# HDMI.net
KiCad netlist of a schematic drawn in Altium Designer
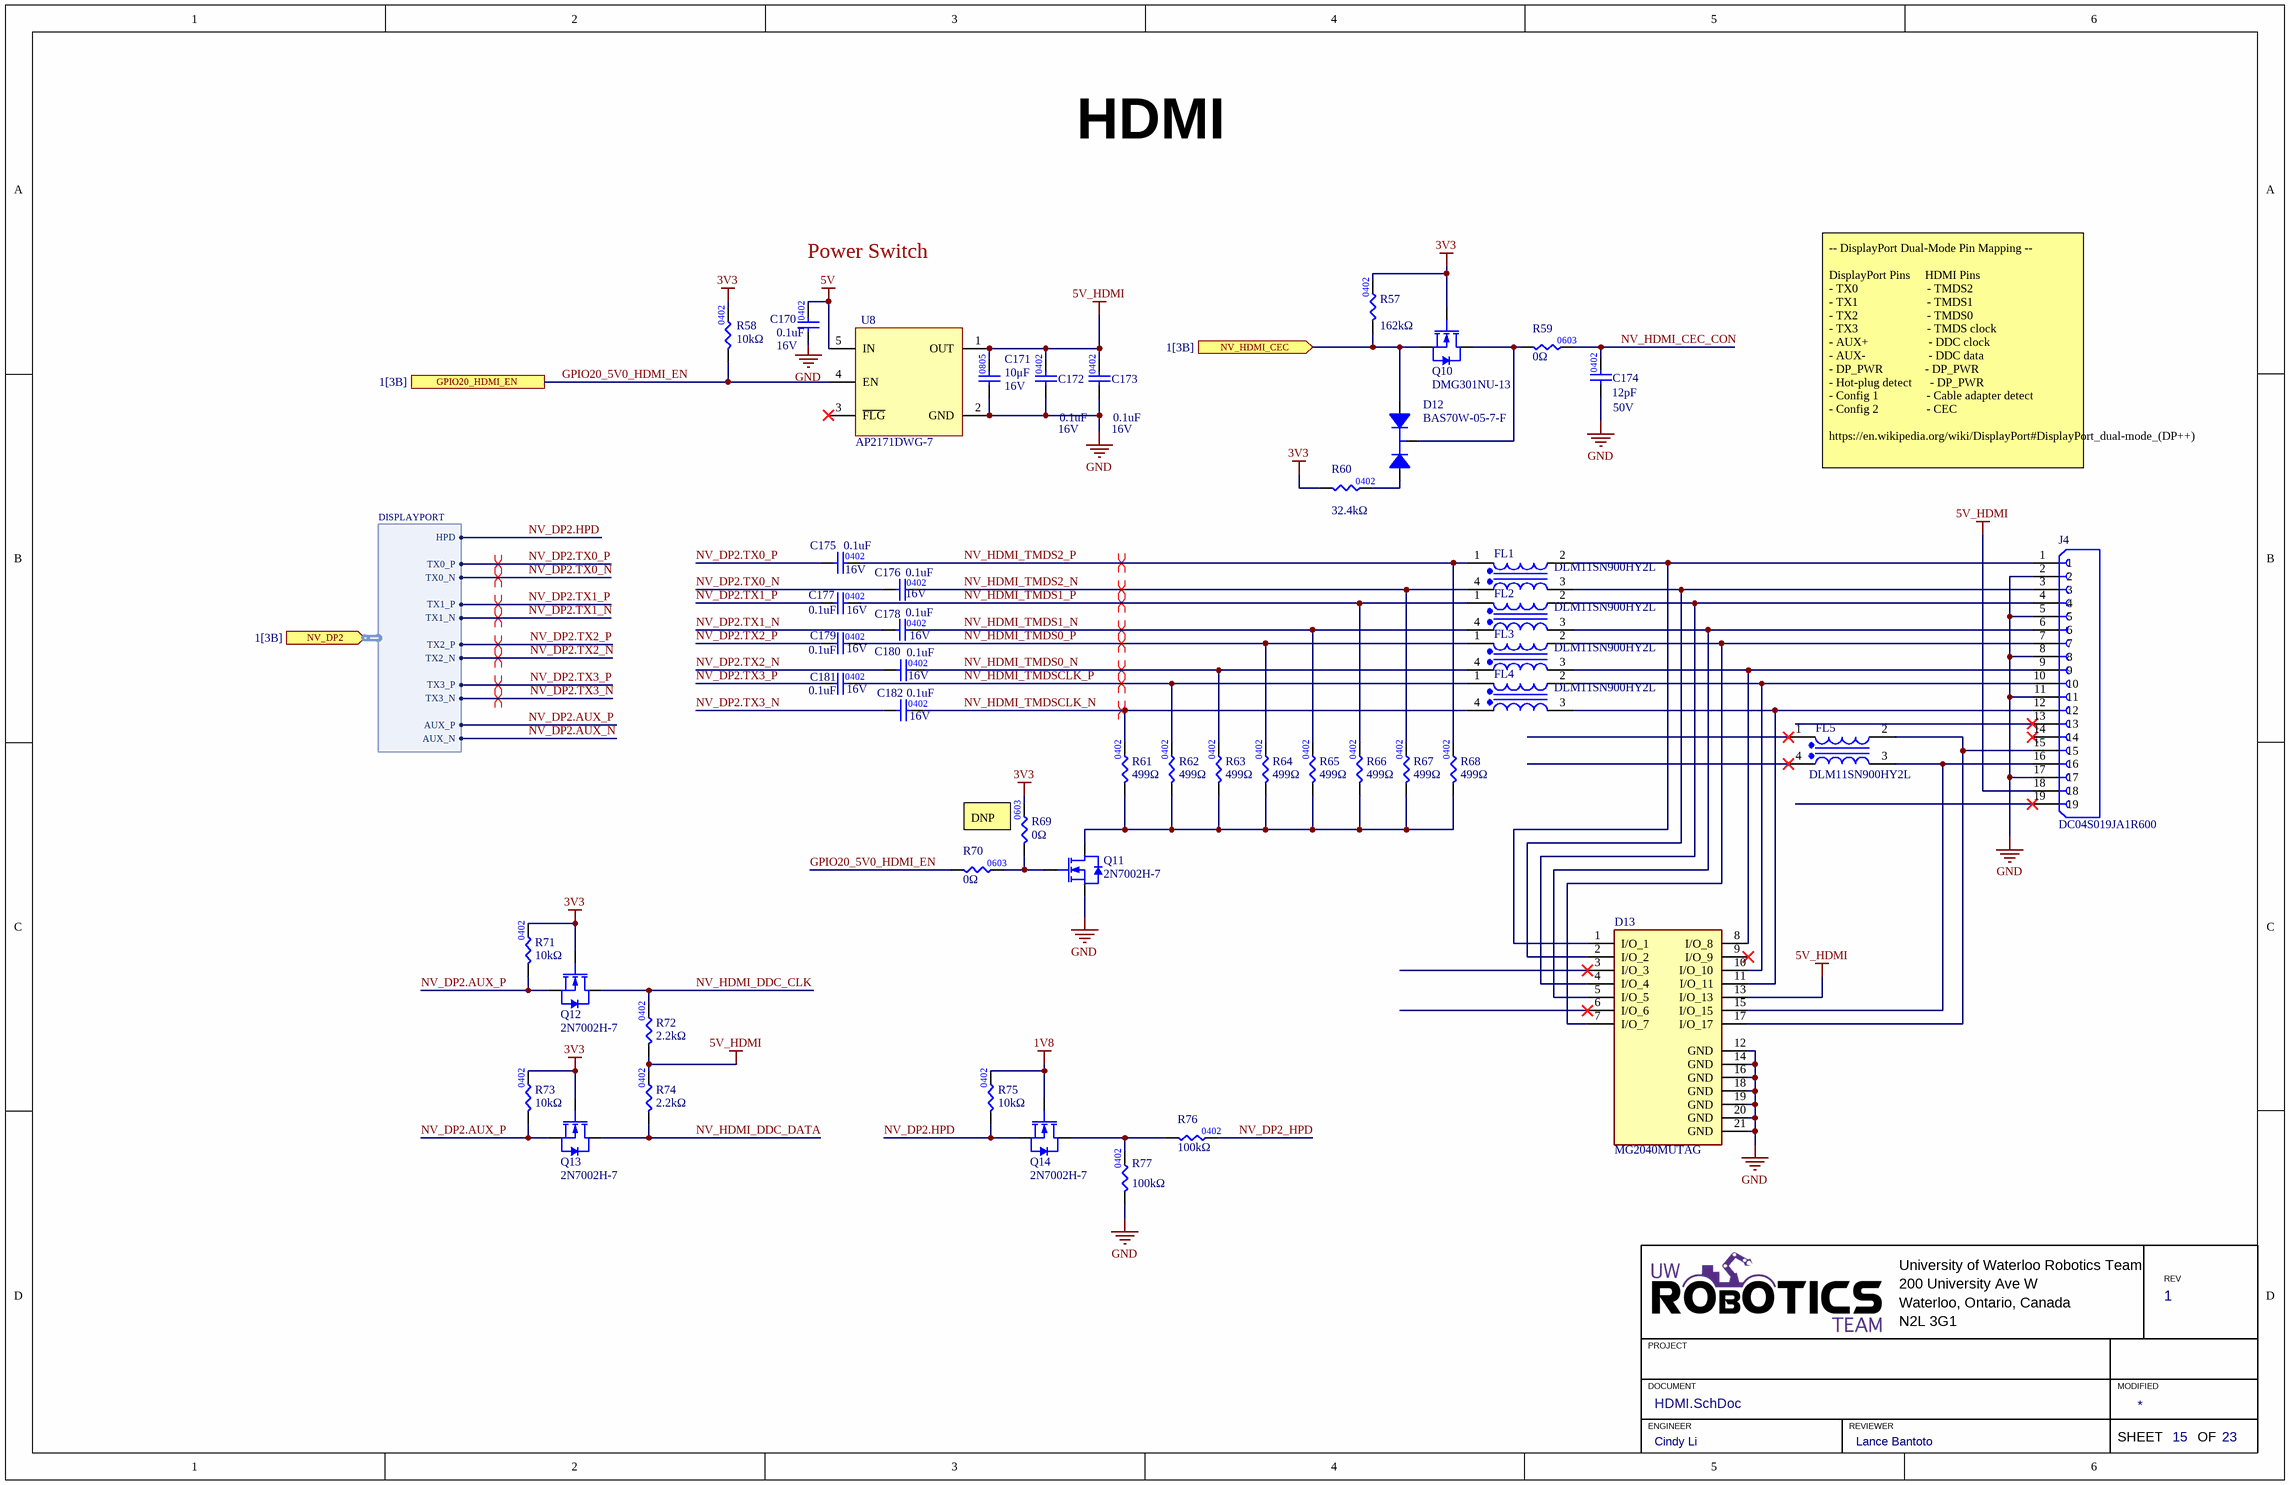
[diagram p0: HDMI.SchDoc]

(export (version "E")
  (design (tool "Eeschema 10.0.6"))
  (components
    (comp (ref "C170")
      (value "CAP_0.1uF_16V_X7R_0402")
      (footprint "CAP0402")
      (description "Ceramic Capacitor, Ceramic")
      (fields
        (field (name "MANUFACTURER") "Taiyo Yuden")
        (field (name "MANUFACTURER PART NUMBER") "LMK212AC6106MD-T")
        (field (name "RATED DC VOLTAGE (URDC)") "16V")
        (field (name "CAPACITANCE") "0.1uF")
      )
      (libsource (lib "UWRT_Schematic_Library_2020") (part "CAP_0.1uF_16V_X7R_0402"))
    )
    (comp (ref "C171")
      (value "10μF")
      (footprint "CAP2012")
      (description "CAP CER 10UF 16V X5R 0805")
      (fields (field (name "VOLTAGE RATING") "16V") (field (name "Comment") "CAP_10uF_16V_0805"))
      (libsource (lib "UWRT_Schematic_Library_2020") (part "CAP_10uF_16V_0805"))
    )
    (comp (ref "C172")
      (value "CAP_0.1uF_16V_X7R_0402")
      (footprint "CAP0402")
      (description "Ceramic Capacitor, Ceramic")
      (fields
        (field (name "MANUFACTURER") "Taiyo Yuden")
        (field (name "MANUFACTURER PART NUMBER") "LMK212AC6106MD-T")
        (field (name "RATED DC VOLTAGE (URDC)") "16V")
        (field (name "CAPACITANCE") "0.1uF")
      )
      (libsource (lib "UWRT_Schematic_Library_2020") (part "CAP_0.1uF_16V_X7R_0402"))
    )
    (comp (ref "C173")
      (value "CAP_0.1uF_16V_X7R_0402")
      (footprint "CAP0402")
      (description "Ceramic Capacitor, Ceramic")
      (fields
        (field (name "MANUFACTURER") "Taiyo Yuden")
        (field (name "MANUFACTURER PART NUMBER") "LMK212AC6106MD-T")
        (field (name "RATED DC VOLTAGE (URDC)") "16V")
        (field (name "CAPACITANCE") "0.1uF")
      )
      (libsource (lib "UWRT_Schematic_Library_2020") (part "CAP_0.1uF_16V_X7R_0402"))
    )
    (comp (ref "C174")
      (value "12pF")
      (footprint "CAP0402")
      (description "CAP CER 12PF 50V C0G 0402")
      (fields
        (field (name "TOLERANCE") "±5%")
        (field (name "VOLTAGE RATING") "50V")
        (field (name "Comment") "CAP_12pF_50V_0402")
      )
      (libsource (lib "UWRT_Schematic_Library_2020") (part "CAP_12pF_50V_0402"))
    )
    (comp (ref "C175")
      (value "CAP_0.1uF_16V_X7R_0402")
      (footprint "CAP0402")
      (description "Ceramic Capacitor, Ceramic")
      (fields
        (field (name "CAPACITANCE") "0.1uF")
        (field (name "MANUFACTURER") "Taiyo Yuden")
        (field (name "MANUFACTURER PART NUMBER") "LMK212AC6106MD-T")
        (field (name "RATED DC VOLTAGE (URDC)") "16V")
      )
      (libsource (lib "UWRT_Schematic_Library_2020") (part "CAP_0.1uF_16V_X7R_0402"))
    )
    (comp (ref "C176")
      (value "CAP_0.1uF_16V_X7R_0402")
      (footprint "CAP0402")
      (description "Ceramic Capacitor, Ceramic")
      (fields
        (field (name "CAPACITANCE") "0.1uF")
        (field (name "MANUFACTURER") "Taiyo Yuden")
        (field (name "MANUFACTURER PART NUMBER") "LMK212AC6106MD-T")
        (field (name "RATED DC VOLTAGE (URDC)") "16V")
      )
      (libsource (lib "UWRT_Schematic_Library_2020") (part "CAP_0.1uF_16V_X7R_0402"))
    )
    (comp (ref "C177")
      (value "CAP_0.1uF_16V_X7R_0402")
      (footprint "CAP0402")
      (description "Ceramic Capacitor, Ceramic")
      (fields
        (field (name "CAPACITANCE") "0.1uF")
        (field (name "MANUFACTURER") "Taiyo Yuden")
        (field (name "MANUFACTURER PART NUMBER") "LMK212AC6106MD-T")
        (field (name "RATED DC VOLTAGE (URDC)") "16V")
      )
      (libsource (lib "UWRT_Schematic_Library_2020") (part "CAP_0.1uF_16V_X7R_0402"))
    )
    (comp (ref "C178")
      (value "CAP_0.1uF_16V_X7R_0402")
      (footprint "CAP0402")
      (description "Ceramic Capacitor, Ceramic")
      (fields
        (field (name "CAPACITANCE") "0.1uF")
        (field (name "MANUFACTURER") "Taiyo Yuden")
        (field (name "MANUFACTURER PART NUMBER") "LMK212AC6106MD-T")
        (field (name "RATED DC VOLTAGE (URDC)") "16V")
      )
      (libsource (lib "UWRT_Schematic_Library_2020") (part "CAP_0.1uF_16V_X7R_0402"))
    )
    (comp (ref "C179")
      (value "CAP_0.1uF_16V_X7R_0402")
      (footprint "CAP0402")
      (description "Ceramic Capacitor, Ceramic")
      (fields
        (field (name "CAPACITANCE") "0.1uF")
        (field (name "MANUFACTURER") "Taiyo Yuden")
        (field (name "MANUFACTURER PART NUMBER") "LMK212AC6106MD-T")
        (field (name "RATED DC VOLTAGE (URDC)") "16V")
      )
      (libsource (lib "UWRT_Schematic_Library_2020") (part "CAP_0.1uF_16V_X7R_0402"))
    )
    (comp (ref "C180")
      (value "CAP_0.1uF_16V_X7R_0402")
      (footprint "CAP0402")
      (description "Ceramic Capacitor, Ceramic")
      (fields
        (field (name "CAPACITANCE") "0.1uF")
        (field (name "MANUFACTURER") "Taiyo Yuden")
        (field (name "MANUFACTURER PART NUMBER") "LMK212AC6106MD-T")
        (field (name "RATED DC VOLTAGE (URDC)") "16V")
      )
      (libsource (lib "UWRT_Schematic_Library_2020") (part "CAP_0.1uF_16V_X7R_0402"))
    )
    (comp (ref "C181")
      (value "CAP_0.1uF_16V_X7R_0402")
      (footprint "CAP0402")
      (description "Ceramic Capacitor, Ceramic")
      (fields
        (field (name "CAPACITANCE") "0.1uF")
        (field (name "MANUFACTURER") "Taiyo Yuden")
        (field (name "MANUFACTURER PART NUMBER") "LMK212AC6106MD-T")
        (field (name "RATED DC VOLTAGE (URDC)") "16V")
      )
      (libsource (lib "UWRT_Schematic_Library_2020") (part "CAP_0.1uF_16V_X7R_0402"))
    )
    (comp (ref "C182")
      (value "CAP_0.1uF_16V_X7R_0402")
      (footprint "CAP0402")
      (description "Ceramic Capacitor, Ceramic")
      (fields
        (field (name "CAPACITANCE") "0.1uF")
        (field (name "MANUFACTURER") "Taiyo Yuden")
        (field (name "MANUFACTURER PART NUMBER") "LMK212AC6106MD-T")
        (field (name "RATED DC VOLTAGE (URDC)") "16V")
      )
      (libsource (lib "UWRT_Schematic_Library_2020") (part "CAP_0.1uF_16V_X7R_0402"))
    )
    (comp (ref "D12")
      (value "BAS70W-05-7-F")
      (footprint "SOT323_BAS70W-05-7-F")
      (description "DIODE ARRAY SCHOTTKY 70V SOT323")
      (libsource (lib "UWRT_Schematic_Library_2020") (part "BAS70W-05-7-F"))
    )
    (comp (ref "D13")
      (value "MG2040MUTAG")
      (footprint "UWRT_Footprint_Library_2020:DIO_MG2040MUTAG")
      (description "10V Clamp 1A (8/20µs) Ipp Tvs Diode Surface Mount 18-UDFN (5.5x1.5)")
      (libsource (lib "UWRT_Schematic_Library_2020") (part "MG2040MUTAG"))
    )
    (comp (ref "FL1")
      (value "DLM11SN900HY2L")
      (footprint "UWRT_Footprint_Library_2020:FIL_DLM11SN900HY2L")
      (description "2 Line Common Mode Choke Surface Mount 90 Ohms @ 100 MHz 100mA DCR 1.38Ohm")
      (libsource (lib "UWRT_Schematic_Library_2020") (part "DLM11SN900HY2L"))
    )
    (comp (ref "FL2")
      (value "DLM11SN900HY2L")
      (footprint "UWRT_Footprint_Library_2020:FIL_DLM11SN900HY2L")
      (description "2 Line Common Mode Choke Surface Mount 90 Ohms @ 100 MHz 100mA DCR 1.38Ohm")
      (libsource (lib "UWRT_Schematic_Library_2020") (part "DLM11SN900HY2L"))
    )
    (comp (ref "FL3")
      (value "DLM11SN900HY2L")
      (footprint "UWRT_Footprint_Library_2020:FIL_DLM11SN900HY2L")
      (description "2 Line Common Mode Choke Surface Mount 90 Ohms @ 100 MHz 100mA DCR 1.38Ohm")
      (libsource (lib "UWRT_Schematic_Library_2020") (part "DLM11SN900HY2L"))
    )
    (comp (ref "FL4")
      (value "DLM11SN900HY2L")
      (footprint "UWRT_Footprint_Library_2020:FIL_DLM11SN900HY2L")
      (description "2 Line Common Mode Choke Surface Mount 90 Ohms @ 100 MHz 100mA DCR 1.38Ohm")
      (libsource (lib "UWRT_Schematic_Library_2020") (part "DLM11SN900HY2L"))
    )
    (comp (ref "FL5")
      (value "DLM11SN900HY2L")
      (footprint "UWRT_Footprint_Library_2020:FIL_DLM11SN900HY2L")
      (description "2 Line Common Mode Choke Surface Mount 90 Ohms @ 100 MHz 100mA DCR 1.38Ohm")
      (libsource (lib "UWRT_Schematic_Library_2020") (part "DLM11SN900HY2L"))
    )
    (comp (ref "J4")
      (value "DC04S019JA1R600")
      (footprint "UWRT_Footprint_Library_2020:JAE_DC04S019JA1R600")
      (description "HDMI HDMI 2.1 Receptacle Connector 19 Position Surface Mount, Right Angle; Through Hole")
      (libsource (lib "UWRT_Schematic_Library_2020") (part "DC04S019JA1R600"))
    )
    (comp (ref "Q10")
      (value "DMG301NU-13")
      (footprint "SOT23-3")
      (description "MOSFET N-CH 25V 260MA SOT23")
      (fields (field (name "MANUFACTURER PART NUMBER 1") "DMG301NU-13"))
      (libsource (lib "UWRT_Schematic_Library_2020") (part "DMG301NU-13"))
    )
    (comp (ref "Q11")
      (value "2N7002H-7")
      (footprint "SOT23-3")
      (description "MOSFET N-CH 60V 170MA SOT23")
      (fields (field (name "MANUFACTURER PART NUMBER 1") "2N7002H-7"))
      (libsource (lib "UWRT_Schematic_Library_2020") (part "2N7002H-7"))
    )
    (comp (ref "Q12")
      (value "2N7002H-7")
      (footprint "SOT23-3")
      (description "MOSFET N-CH 60V 170MA SOT23")
      (fields (field (name "MANUFACTURER PART NUMBER 1") "2N7002H-7"))
      (libsource (lib "UWRT_Schematic_Library_2020") (part "2N7002H-7"))
    )
    (comp (ref "Q13")
      (value "2N7002H-7")
      (footprint "SOT23-3")
      (description "MOSFET N-CH 60V 170MA SOT23")
      (fields (field (name "MANUFACTURER PART NUMBER 1") "2N7002H-7"))
      (libsource (lib "UWRT_Schematic_Library_2020") (part "2N7002H-7"))
    )
    (comp (ref "Q14")
      (value "2N7002H-7")
      (footprint "SOT23-3")
      (description "MOSFET N-CH 60V 170MA SOT23")
      (fields (field (name "MANUFACTURER PART NUMBER 1") "2N7002H-7"))
      (libsource (lib "UWRT_Schematic_Library_2020") (part "2N7002H-7"))
    )
    (comp (ref "R57")
      (value "162kΩ")
      (footprint "RES0402")
      (description "RES 162K OHM 1% 1/16W 0402")
      (fields (field (name "POWER") "0.063W, 1/16W") (field (name "TOLERANCE") "1%"))
      (libsource (lib "UWRT_Schematic_Library_2020") (part "RES_162kΩ_0402_1%"))
    )
    (comp (ref "R58")
      (value "10kΩ")
      (footprint "RES0402")
      (description "RES SMD 10K OHM 1% 1/16W 0402")
      (fields (field (name "POWER") "0.063W, 1/16W") (field (name "TOLERANCE") "1%"))
      (libsource (lib "UWRT_Schematic_Library_2020") (part "RES_10kΩ_0402_1%"))
    )
    (comp (ref "R59")
      (value "0Ω")
      (footprint "RES0603")
      (description "RES 0 OHM JUMPER 1/10W 0603")
      (fields (field (name "Comment") "RES_0Ω_0603"))
      (libsource (lib "UWRT_Schematic_Library_2020") (part "RES_0Ω_0603"))
    )
    (comp (ref "R60")
      (value "32.4kΩ")
      (footprint "RES0402")
      (description "RES SMD 32.4K OHM 1% 1/10W 0402")
      (fields (field (name "POWER") "0.1W, 1/10W") (field (name "TOLERANCE") "1%"))
      (libsource (lib "UWRT_Schematic_Library_2020") (part "RES_32.4kΩ_0402_1%"))
    )
    (comp (ref "R61")
      (value "499Ω")
      (footprint "RES0402")
      (description "RES 499 OHM 1% 1/16W 0402")
      (fields (field (name "POWER") "0.063W, 1/16W") (field (name "TOLERANCE") "1%"))
      (libsource (lib "UWRT_Schematic_Library_2020") (part "RES_499Ω_0402_1%"))
    )
    (comp (ref "R62")
      (value "499Ω")
      (footprint "RES0402")
      (description "RES 499 OHM 1% 1/16W 0402")
      (fields (field (name "POWER") "0.063W, 1/16W") (field (name "TOLERANCE") "1%"))
      (libsource (lib "UWRT_Schematic_Library_2020") (part "RES_499Ω_0402_1%"))
    )
    (comp (ref "R63")
      (value "499Ω")
      (footprint "RES0402")
      (description "RES 499 OHM 1% 1/16W 0402")
      (fields (field (name "POWER") "0.063W, 1/16W") (field (name "TOLERANCE") "1%"))
      (libsource (lib "UWRT_Schematic_Library_2020") (part "RES_499Ω_0402_1%"))
    )
    (comp (ref "R64")
      (value "499Ω")
      (footprint "RES0402")
      (description "RES 499 OHM 1% 1/16W 0402")
      (fields (field (name "POWER") "0.063W, 1/16W") (field (name "TOLERANCE") "1%"))
      (libsource (lib "UWRT_Schematic_Library_2020") (part "RES_499Ω_0402_1%"))
    )
    (comp (ref "R65")
      (value "499Ω")
      (footprint "RES0402")
      (description "RES 499 OHM 1% 1/16W 0402")
      (fields (field (name "POWER") "0.063W, 1/16W") (field (name "TOLERANCE") "1%"))
      (libsource (lib "UWRT_Schematic_Library_2020") (part "RES_499Ω_0402_1%"))
    )
    (comp (ref "R66")
      (value "499Ω")
      (footprint "RES0402")
      (description "RES 499 OHM 1% 1/16W 0402")
      (fields (field (name "POWER") "0.063W, 1/16W") (field (name "TOLERANCE") "1%"))
      (libsource (lib "UWRT_Schematic_Library_2020") (part "RES_499Ω_0402_1%"))
    )
    (comp (ref "R67")
      (value "499Ω")
      (footprint "RES0402")
      (description "RES 499 OHM 1% 1/16W 0402")
      (fields (field (name "POWER") "0.063W, 1/16W") (field (name "TOLERANCE") "1%"))
      (libsource (lib "UWRT_Schematic_Library_2020") (part "RES_499Ω_0402_1%"))
    )
    (comp (ref "R68")
      (value "499Ω")
      (footprint "RES0402")
      (description "RES 499 OHM 1% 1/16W 0402")
      (fields (field (name "POWER") "0.063W, 1/16W") (field (name "TOLERANCE") "1%"))
      (libsource (lib "UWRT_Schematic_Library_2020") (part "RES_499Ω_0402_1%"))
    )
    (comp (ref "R69")
      (value "0Ω")
      (footprint "RES0603")
      (description "RES 0 OHM JUMPER 1/10W 0603")
      (fields (field (name "Comment") "RES_0Ω_0603"))
      (libsource (lib "UWRT_Schematic_Library_2020") (part "RES_0Ω_0603"))
    )
    (comp (ref "R70")
      (value "0Ω")
      (footprint "RES0603")
      (description "RES 0 OHM JUMPER 1/10W 0603")
      (fields (field (name "Comment") "RES_0Ω_0603"))
      (libsource (lib "UWRT_Schematic_Library_2020") (part "RES_0Ω_0603"))
    )
    (comp (ref "R71")
      (value "10kΩ")
      (footprint "RES0402")
      (description "RES SMD 10K OHM 1% 1/16W 0402")
      (fields (field (name "POWER") "0.063W, 1/16W") (field (name "TOLERANCE") "1%"))
      (libsource (lib "UWRT_Schematic_Library_2020") (part "RES_10kΩ_0402_1%"))
    )
    (comp (ref "R72")
      (value "2.2kΩ")
      (footprint "RES0402")
      (description "RES SMD 2.2K OHM 5% 1/10W 0402")
      (fields (field (name "Comment") "RES_2.2kΩ_0402_5%"))
      (libsource (lib "UWRT_Schematic_Library_2020") (part "RES_2.2kΩ_0402_5%"))
    )
    (comp (ref "R73")
      (value "10kΩ")
      (footprint "RES0402")
      (description "RES SMD 10K OHM 1% 1/16W 0402")
      (fields (field (name "POWER") "0.063W, 1/16W") (field (name "TOLERANCE") "1%"))
      (libsource (lib "UWRT_Schematic_Library_2020") (part "RES_10kΩ_0402_1%"))
    )
    (comp (ref "R74")
      (value "2.2kΩ")
      (footprint "RES0402")
      (description "RES SMD 2.2K OHM 5% 1/10W 0402")
      (fields (field (name "Comment") "RES_2.2kΩ_0402_5%"))
      (libsource (lib "UWRT_Schematic_Library_2020") (part "RES_2.2kΩ_0402_5%"))
    )
    (comp (ref "R75")
      (value "10kΩ")
      (footprint "RES0402")
      (description "RES SMD 10K OHM 1% 1/16W 0402")
      (fields (field (name "POWER") "0.063W, 1/16W") (field (name "TOLERANCE") "1%"))
      (libsource (lib "UWRT_Schematic_Library_2020") (part "RES_10kΩ_0402_1%"))
    )
    (comp (ref "R76")
      (value "100kΩ")
      (footprint "RES0402")
      (description "RES SMD 100K OHM 5% 1/10W 0402")
      (fields (field (name "POWER") "0.1W, 1/10W") (field (name "TOLERANCE") "5%"))
      (libsource (lib "UWRT_Schematic_Library_2020") (part "RES_100kΩ_0402_5%"))
    )
    (comp (ref "R77")
      (value "100kΩ")
      (footprint "RES0402")
      (description "RES SMD 100K OHM 5% 1/10W 0402")
      (fields (field (name "POWER") "0.1W, 1/10W") (field (name "TOLERANCE") "5%"))
      (libsource (lib "UWRT_Schematic_Library_2020") (part "RES_100kΩ_0402_5%"))
    )
    (comp (ref "U8")
      (value "AP2171DWG-7")
      (footprint "AP2171DWG-7")
      (description "Power Switch/Driver 1:1 P-Channel 1A SOT-25")
      (libsource (lib "UWRT_Schematic_Library_2020") (part "AP2171DWG-7"))
    )
  )
  (nets
    (net (code "2") (name "/GPIO20_5V0_HDMI_EN") (class "Default")
      (node (ref "R58") (pin "1") (pinfunction "1_1") (pintype "passive"))
      (node (ref "R70") (pin "1") (pinfunction "1_1") (pintype "passive"))
      (node (ref "U8") (pin "4") (pinfunction "EN_4") (pintype "passive"))
    )
    (net (code "4") (name "/NV_DP2.AUX_P") (class "Default")
      (node (ref "Q12") (pin "2") (pinfunction "SOURCE_2") (pintype "passive"))
      (node (ref "Q13") (pin "2") (pinfunction "SOURCE_2") (pintype "passive"))
      (node (ref "R71") (pin "1") (pinfunction "1_1") (pintype "passive"))
      (node (ref "R73") (pin "1") (pinfunction "1_1") (pintype "passive"))
    )
    (net (code "5") (name "/NV_DP2.HPD") (class "Default")
      (node (ref "Q14") (pin "2") (pinfunction "SOURCE_2") (pintype "passive"))
      (node (ref "R75") (pin "1") (pinfunction "1_1") (pintype "passive"))
    )
    (net (code "6") (name "/NV_DP2.TX0_N") (class "Default")
      (node (ref "C176") (pin "1") (pinfunction "1_1") (pintype "passive"))
    )
    (net (code "7") (name "/NV_DP2.TX0_P") (class "Default")
      (node (ref "C175") (pin "1") (pinfunction "1_1") (pintype "passive"))
    )
    (net (code "8") (name "/NV_DP2.TX1_N") (class "Default")
      (node (ref "C178") (pin "1") (pinfunction "1_1") (pintype "passive"))
    )
    (net (code "9") (name "/NV_DP2.TX1_P") (class "Default")
      (node (ref "C177") (pin "1") (pinfunction "1_1") (pintype "passive"))
    )
    (net (code "10") (name "/NV_DP2.TX2_N") (class "Default")
      (node (ref "C180") (pin "1") (pinfunction "1_1") (pintype "passive"))
    )
    (net (code "11") (name "/NV_DP2.TX2_P") (class "Default")
      (node (ref "C179") (pin "1") (pinfunction "1_1") (pintype "passive"))
    )
    (net (code "12") (name "/NV_DP2.TX3_N") (class "Default")
      (node (ref "C182") (pin "1") (pinfunction "1_1") (pintype "passive"))
    )
    (net (code "13") (name "/NV_DP2.TX3_P") (class "Default")
      (node (ref "C181") (pin "1") (pinfunction "1_1") (pintype "passive"))
    )
    (net (code "14") (name "/NV_DP2_HPD") (class "Default")
      (node (ref "R76") (pin "2") (pinfunction "2_2") (pintype "passive"))
    )
    (net (code "15") (name "/NV_HDMI_CEC") (class "Default")
      (node (ref "D12") (pin "2") (pintype "passive"))
      (node (ref "Q10") (pin "2") (pinfunction "SOURCE_2") (pintype "passive"))
      (node (ref "R57") (pin "1") (pinfunction "1_1") (pintype "passive"))
    )
    (net (code "16") (name "/NV_HDMI_CEC_CON") (class "Default")
      (node (ref "C174") (pin "2") (pinfunction "2_2") (pintype "passive"))
      (node (ref "R59") (pin "2") (pinfunction "2_2") (pintype "passive"))
    )
    (net (code "17") (name "/NV_HDMI_DDC_CLK") (class "Default")
      (node (ref "Q12") (pin "3") (pinfunction "DRAIN_3") (pintype "passive"))
      (node (ref "R72") (pin "2") (pinfunction "2_2") (pintype "passive"))
    )
    (net (code "18") (name "/NV_HDMI_DDC_DATA") (class "Default")
      (node (ref "Q13") (pin "3") (pinfunction "DRAIN_3") (pintype "passive"))
      (node (ref "R74") (pin "1") (pinfunction "1_1") (pintype "passive"))
    )
    (net (code "19") (name "/NV_HDMI_TMDS0_N") (class "Default")
      (node (ref "C180") (pin "2") (pinfunction "2_2") (pintype "passive"))
      (node (ref "FL3") (pin "4") (pinfunction "4_4") (pintype "passive"))
      (node (ref "R63") (pin "2") (pinfunction "2_2") (pintype "passive"))
    )
    (net (code "20") (name "/NV_HDMI_TMDS0_P") (class "Default")
      (node (ref "C179") (pin "2") (pinfunction "2_2") (pintype "passive"))
      (node (ref "FL3") (pin "1") (pinfunction "1_1") (pintype "passive"))
      (node (ref "R64") (pin "2") (pinfunction "2_2") (pintype "passive"))
    )
    (net (code "21") (name "/NV_HDMI_TMDS1_N") (class "Default")
      (node (ref "C178") (pin "2") (pinfunction "2_2") (pintype "passive"))
      (node (ref "FL2") (pin "4") (pinfunction "4_4") (pintype "passive"))
      (node (ref "R65") (pin "2") (pinfunction "2_2") (pintype "passive"))
    )
    (net (code "22") (name "/NV_HDMI_TMDS1_P") (class "Default")
      (node (ref "C177") (pin "2") (pinfunction "2_2") (pintype "passive"))
      (node (ref "FL2") (pin "1") (pinfunction "1_1") (pintype "passive"))
      (node (ref "R66") (pin "2") (pinfunction "2_2") (pintype "passive"))
    )
    (net (code "23") (name "/NV_HDMI_TMDS2_N") (class "Default")
      (node (ref "C176") (pin "2") (pinfunction "2_2") (pintype "passive"))
      (node (ref "FL1") (pin "4") (pinfunction "4_4") (pintype "passive"))
      (node (ref "R67") (pin "2") (pinfunction "2_2") (pintype "passive"))
    )
    (net (code "24") (name "/NV_HDMI_TMDS2_P") (class "Default")
      (node (ref "C175") (pin "2") (pinfunction "2_2") (pintype "passive"))
      (node (ref "FL1") (pin "1") (pinfunction "1_1") (pintype "passive"))
      (node (ref "R68") (pin "2") (pinfunction "2_2") (pintype "passive"))
    )
    (net (code "25") (name "/NV_HDMI_TMDSCLK_N") (class "Default")
      (node (ref "C182") (pin "2") (pinfunction "2_2") (pintype "passive"))
      (node (ref "FL4") (pin "4") (pinfunction "4_4") (pintype "passive"))
      (node (ref "R61") (pin "2") (pinfunction "2_2") (pintype "passive"))
    )
    (net (code "26") (name "/NV_HDMI_TMDSCLK_P") (class "Default")
      (node (ref "C181") (pin "2") (pinfunction "2_2") (pintype "passive"))
      (node (ref "FL4") (pin "1") (pinfunction "1_1") (pintype "passive"))
      (node (ref "R62") (pin "2") (pinfunction "2_2") (pintype "passive"))
    )
    (net (code "28") (name "1V8") (class "Default")
      (node (ref "Q14") (pin "1") (pinfunction "GATE_1") (pintype "passive"))
      (node (ref "R75") (pin "2") (pinfunction "2_2") (pintype "passive"))
    )
    (net (code "29") (name "3V3") (class "Default")
      (node (ref "Q10") (pin "1") (pinfunction "GATE_1") (pintype "passive"))
      (node (ref "Q12") (pin "1") (pinfunction "GATE_1") (pintype "passive"))
      (node (ref "Q13") (pin "1") (pinfunction "GATE_1") (pintype "passive"))
      (node (ref "R57") (pin "2") (pinfunction "2_2") (pintype "passive"))
      (node (ref "R58") (pin "2") (pinfunction "2_2") (pintype "passive"))
      (node (ref "R60") (pin "1") (pinfunction "1_1") (pintype "passive"))
      (node (ref "R69") (pin "2") (pinfunction "2_2") (pintype "passive"))
      (node (ref "R71") (pin "2") (pinfunction "2_2") (pintype "passive"))
      (node (ref "R73") (pin "2") (pinfunction "2_2") (pintype "passive"))
    )
    (net (code "30") (name "5V") (class "Default")
      (node (ref "C170") (pin "2") (pinfunction "2_2") (pintype "passive"))
      (node (ref "U8") (pin "5") (pinfunction "IN_5") (pintype "passive"))
    )
    (net (code "31") (name "5V_HDMI") (class "Default")
      (node (ref "C171") (pin "2") (pinfunction "2_2") (pintype "passive"))
      (node (ref "C172") (pin "2") (pinfunction "2_2") (pintype "passive"))
      (node (ref "C173") (pin "2") (pinfunction "2_2") (pintype "passive"))
      (node (ref "D13") (pin "13") (pinfunction "I/O_13_13") (pintype "passive"))
      (node (ref "J4") (pin "18") (pinfunction "18_18") (pintype "passive"))
      (node (ref "R72") (pin "1") (pinfunction "1_1") (pintype "passive"))
      (node (ref "R74") (pin "2") (pinfunction "2_2") (pintype "passive"))
      (node (ref "U8") (pin "1") (pinfunction "OUT_1") (pintype "passive"))
    )
    (net (code "32") (name "GND") (class "Default")
      (node (ref "C170") (pin "1") (pinfunction "1_1") (pintype "passive"))
      (node (ref "C171") (pin "1") (pinfunction "1_1") (pintype "passive"))
      (node (ref "C172") (pin "1") (pinfunction "1_1") (pintype "passive"))
      (node (ref "C173") (pin "1") (pinfunction "1_1") (pintype "passive"))
      (node (ref "C174") (pin "1") (pinfunction "1_1") (pintype "passive"))
      (node (ref "D13") (pin "12") (pinfunction "GND_12") (pintype "power_in"))
      (node (ref "D13") (pin "14") (pinfunction "GND_14") (pintype "power_in"))
      (node (ref "D13") (pin "16") (pinfunction "GND_16") (pintype "power_in"))
      (node (ref "D13") (pin "18") (pinfunction "GND_18") (pintype "power_in"))
      (node (ref "D13") (pin "19") (pinfunction "GND_19") (pintype "power_in"))
      (node (ref "D13") (pin "20") (pinfunction "GND_20") (pintype "power_in"))
      (node (ref "D13") (pin "21") (pinfunction "GND_21") (pintype "power_in"))
      (node (ref "J4") (pin "11") (pinfunction "11_11") (pintype "passive"))
      (node (ref "J4") (pin "17") (pinfunction "17_17") (pintype "passive"))
      (node (ref "J4") (pin "2") (pinfunction "2_2") (pintype "passive"))
      (node (ref "J4") (pin "5") (pinfunction "5_5") (pintype "passive"))
      (node (ref "J4") (pin "8") (pinfunction "8_8") (pintype "passive"))
      (node (ref "Q11") (pin "2") (pinfunction "SOURCE_2") (pintype "passive"))
      (node (ref "R77") (pin "1") (pinfunction "1_1") (pintype "passive"))
      (node (ref "U8") (pin "2") (pinfunction "GND_2") (pintype "passive"))
    )
    (net (code "33") (name "Net-(D12-Pad1)") (class "Default")
      (node (ref "D12") (pin "1") (pintype "passive"))
      (node (ref "R60") (pin "2") (pinfunction "2_2") (pintype "passive"))
    )
    (net (code "34") (name "Net-(D13-I{slash}O_1)") (class "Default")
      (node (ref "D13") (pin "1") (pinfunction "I/O_1_1") (pintype "passive"))
      (node (ref "FL1") (pin "2") (pinfunction "2_2") (pintype "passive"))
      (node (ref "J4") (pin "1") (pinfunction "1_1") (pintype "passive"))
    )
    (net (code "35") (name "Net-(D13-I{slash}O_2)") (class "Default")
      (node (ref "D13") (pin "2") (pinfunction "I/O_2_2") (pintype "passive"))
      (node (ref "FL1") (pin "3") (pinfunction "3_3") (pintype "passive"))
      (node (ref "J4") (pin "3") (pinfunction "3_3") (pintype "passive"))
    )
    (net (code "36") (name "Net-(D13-I{slash}O_4)") (class "Default")
      (node (ref "D13") (pin "4") (pinfunction "I/O_4_4") (pintype "passive"))
      (node (ref "FL2") (pin "2") (pinfunction "2_2") (pintype "passive"))
      (node (ref "J4") (pin "4") (pinfunction "4_4") (pintype "passive"))
    )
    (net (code "37") (name "Net-(D13-I{slash}O_5)") (class "Default")
      (node (ref "D13") (pin "5") (pinfunction "I/O_5_5") (pintype "passive"))
      (node (ref "FL2") (pin "3") (pinfunction "3_3") (pintype "passive"))
      (node (ref "J4") (pin "6") (pinfunction "6_6") (pintype "passive"))
    )
    (net (code "38") (name "Net-(D13-I{slash}O_7)") (class "Default")
      (node (ref "D13") (pin "7") (pinfunction "I/O_7_7") (pintype "passive"))
      (node (ref "FL3") (pin "2") (pinfunction "2_2") (pintype "passive"))
      (node (ref "J4") (pin "7") (pinfunction "7_7") (pintype "passive"))
    )
    (net (code "39") (name "Net-(D13-I{slash}O_8)") (class "Default")
      (node (ref "D13") (pin "8") (pinfunction "I/O_8_8") (pintype "passive"))
      (node (ref "FL3") (pin "3") (pinfunction "3_3") (pintype "passive"))
      (node (ref "J4") (pin "9") (pinfunction "9_9") (pintype "passive"))
    )
    (net (code "40") (name "Net-(D13-I{slash}O_10)") (class "Default")
      (node (ref "D13") (pin "10") (pinfunction "I/O_10_10") (pintype "passive"))
      (node (ref "FL4") (pin "2") (pinfunction "2_2") (pintype "passive"))
      (node (ref "J4") (pin "10") (pinfunction "10_10") (pintype "passive"))
    )
    (net (code "41") (name "Net-(D13-I{slash}O_11)") (class "Default")
      (node (ref "D13") (pin "11") (pinfunction "I/O_11_11") (pintype "passive"))
      (node (ref "FL4") (pin "3") (pinfunction "3_3") (pintype "passive"))
      (node (ref "J4") (pin "12") (pinfunction "12_12") (pintype "passive"))
    )
    (net (code "42") (name "Net-(D13-I{slash}O_15)") (class "Default")
      (node (ref "D13") (pin "15") (pinfunction "I/O_15_15") (pintype "passive"))
      (node (ref "FL5") (pin "3") (pinfunction "3_3") (pintype "passive"))
      (node (ref "J4") (pin "16") (pinfunction "16_16") (pintype "passive"))
    )
    (net (code "43") (name "Net-(D13-I{slash}O_17)") (class "Default")
      (node (ref "D13") (pin "17") (pinfunction "I/O_17_17") (pintype "passive"))
      (node (ref "FL5") (pin "2") (pinfunction "2_2") (pintype "passive"))
      (node (ref "J4") (pin "15") (pinfunction "15_15") (pintype "passive"))
    )
    (net (code "44") (name "Net-(Q10-DRAIN)") (class "Default")
      (node (ref "D12") (pin "3") (pintype "passive"))
      (node (ref "Q10") (pin "3") (pinfunction "DRAIN_3") (pintype "passive"))
      (node (ref "R59") (pin "1") (pinfunction "1_1") (pintype "passive"))
    )
    (net (code "45") (name "Net-(Q11-DRAIN)") (class "Default")
      (node (ref "Q11") (pin "3") (pinfunction "DRAIN_3") (pintype "passive"))
      (node (ref "R61") (pin "1") (pinfunction "1_1") (pintype "passive"))
      (node (ref "R62") (pin "1") (pinfunction "1_1") (pintype "passive"))
      (node (ref "R63") (pin "1") (pinfunction "1_1") (pintype "passive"))
      (node (ref "R64") (pin "1") (pinfunction "1_1") (pintype "passive"))
      (node (ref "R65") (pin "1") (pinfunction "1_1") (pintype "passive"))
      (node (ref "R66") (pin "1") (pinfunction "1_1") (pintype "passive"))
      (node (ref "R67") (pin "1") (pinfunction "1_1") (pintype "passive"))
      (node (ref "R68") (pin "1") (pinfunction "1_1") (pintype "passive"))
    )
    (net (code "46") (name "Net-(Q11-GATE)") (class "Default")
      (node (ref "Q11") (pin "1") (pinfunction "GATE_1") (pintype "passive"))
      (node (ref "R69") (pin "1") (pinfunction "1_1") (pintype "passive"))
      (node (ref "R70") (pin "2") (pinfunction "2_2") (pintype "passive"))
    )
    (net (code "47") (name "Net-(Q14-DRAIN)") (class "Default")
      (node (ref "Q14") (pin "3") (pinfunction "DRAIN_3") (pintype "passive"))
      (node (ref "R76") (pin "1") (pinfunction "1_1") (pintype "passive"))
      (node (ref "R77") (pin "2") (pinfunction "2_2") (pintype "passive"))
    )
    (net (code "48") (name "unconnected-(D13-I{slash}O_3-Pad3)") (class "Default")
      (node (ref "D13") (pin "3") (pinfunction "I/O_3_3") (pintype "passive+no_connect"))
    )
    (net (code "49") (name "unconnected-(D13-I{slash}O_6-Pad6)") (class "Default")
      (node (ref "D13") (pin "6") (pinfunction "I/O_6_6") (pintype "passive+no_connect"))
    )
    (net (code "50") (name "unconnected-(D13-I{slash}O_9-Pad9)") (class "Default")
      (node (ref "D13") (pin "9") (pinfunction "I/O_9_9") (pintype "passive+no_connect"))
    )
    (net (code "51") (name "unconnected-(FL5-Pad1)") (class "Default")
      (node (ref "FL5") (pin "1") (pinfunction "1_1") (pintype "passive+no_connect"))
    )
    (net (code "52") (name "unconnected-(FL5-Pad4)") (class "Default")
      (node (ref "FL5") (pin "4") (pinfunction "4_4") (pintype "passive+no_connect"))
    )
    (net (code "53") (name "unconnected-(J4-Pad13)") (class "Default")
      (node (ref "J4") (pin "13") (pinfunction "13_13") (pintype "passive+no_connect"))
    )
    (net (code "54") (name "unconnected-(J4-Pad14)") (class "Default")
      (node (ref "J4") (pin "14") (pinfunction "14_14") (pintype "passive+no_connect"))
    )
    (net (code "55") (name "unconnected-(J4-Pad19)") (class "Default")
      (node (ref "J4") (pin "19") (pinfunction "19_19") (pintype "passive+no_connect"))
    )
    (net (code "56") (name "unconnected-(U8-~{FLG}-Pad3)") (class "Default")
      (node (ref "U8") (pin "3") (pinfunction "~{FLG}_3") (pintype "passive+no_connect"))
    )
  )
)
